# pixelAdapter_f103c8.net
KiCad netlist of a schematic drawn in EAGLE
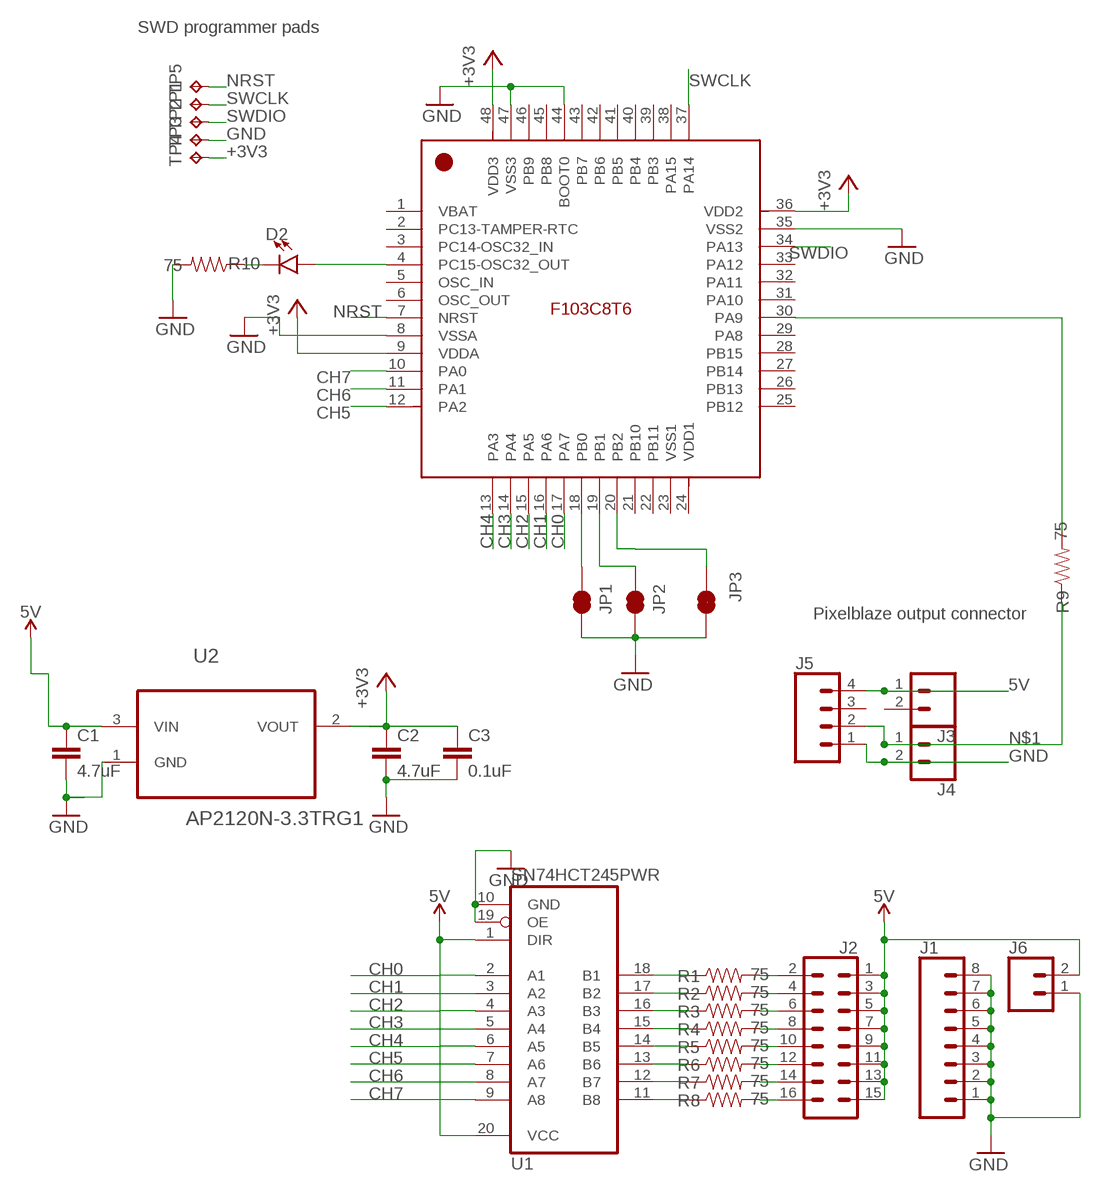
[diagram p0: schematic, sheet 1]

(export (version "E")
  (design (tool "Eeschema 10.0.6"))
  (components
    (comp (ref "C1")
      (value "4.7uF")
      (footprint "eagle-import:0603")
      (libsource (lib "eagle-import") (part "4.7UF0603"))
    )
    (comp (ref "C2")
      (value "4.7uF")
      (footprint "eagle-import:0603")
      (libsource (lib "eagle-import") (part "4.7UF0603"))
    )
    (comp (ref "C3")
      (value "0.1uF")
      (footprint "eagle-import:0603")
      (libsource (lib "eagle-import") (part "0.1UF-0603-25V-(+80/-20%)"))
    )
    (comp (ref "D2")
      (value "LED0603")
      (footprint "eagle-import:LED-0603")
      (libsource (lib "eagle-import") (part "LED0603"))
    )
    (comp (ref "J1")
      (value "CONN_08\"")
      (footprint "eagle-import:1X08")
      (libsource (lib "eagle-import") (part "CONN_08{dblquote}"))
    )
    (comp (ref "J2")
      (value "CONN_08X2")
      (footprint "eagle-import:2X8")
      (libsource (lib "eagle-import") (part "CONN_08X2"))
    )
    (comp (ref "J3")
      (value "CONN_025MM")
      (footprint "eagle-import:SCREWTERMINAL-5MM-2")
      (libsource (lib "eagle-import") (part "bens_CONN_025MM"))
    )
    (comp (ref "J4")
      (value "CONN_025MM")
      (footprint "eagle-import:SCREWTERMINAL-5MM-2")
      (libsource (lib "eagle-import") (part "bens_CONN_025MM"))
    )
    (comp (ref "J5")
      (value "CONN_04LOCK")
      (footprint "eagle-import:1X04_LOCK")
      (libsource (lib "eagle-import") (part "CONN_04LOCK"))
    )
    (comp (ref "J6")
      (value "CONN_02")
      (footprint "eagle-import:1X02")
      (libsource (lib "eagle-import") (part "CONN_02"))
    )
    (comp (ref "JP1")
      (value "JUMPER-SMT_2_NC_TRACE_SILK")
      (footprint "eagle-import:SMT-JUMPER_2_NC_TRACE_SILK")
      (libsource (lib "eagle-import") (part "JUMPER-SMT_2_NC_TRACE_SILK"))
    )
    (comp (ref "JP2")
      (value "JUMPER-SMT_2_NC_TRACE_SILK")
      (footprint "eagle-import:SMT-JUMPER_2_NC_TRACE_SILK")
      (libsource (lib "eagle-import") (part "JUMPER-SMT_2_NC_TRACE_SILK"))
    )
    (comp (ref "JP3")
      (value "JUMPER-SMT_2_NC_TRACE_SILK")
      (footprint "eagle-import:SMT-JUMPER_2_NC_TRACE_SILK")
      (libsource (lib "eagle-import") (part "JUMPER-SMT_2_NC_TRACE_SILK"))
    )
    (comp (ref "R1")
      (value "75")
      (footprint "eagle-import:0603")
      (libsource (lib "eagle-import") (part "100OHM-0603-1/4W-5%"))
    )
    (comp (ref "R2")
      (value "75")
      (footprint "eagle-import:0603")
      (libsource (lib "eagle-import") (part "100OHM-0603-1/4W-5%"))
    )
    (comp (ref "R3")
      (value "75")
      (footprint "eagle-import:0603")
      (libsource (lib "eagle-import") (part "100OHM-0603-1/4W-5%"))
    )
    (comp (ref "R4")
      (value "75")
      (footprint "eagle-import:0603")
      (libsource (lib "eagle-import") (part "100OHM-0603-1/4W-5%"))
    )
    (comp (ref "R5")
      (value "75")
      (footprint "eagle-import:0603")
      (libsource (lib "eagle-import") (part "100OHM-0603-1/4W-5%"))
    )
    (comp (ref "R6")
      (value "75")
      (footprint "eagle-import:0603")
      (libsource (lib "eagle-import") (part "100OHM-0603-1/4W-5%"))
    )
    (comp (ref "R7")
      (value "75")
      (footprint "eagle-import:0603")
      (libsource (lib "eagle-import") (part "100OHM-0603-1/4W-5%"))
    )
    (comp (ref "R8")
      (value "75")
      (footprint "eagle-import:0603")
      (libsource (lib "eagle-import") (part "100OHM-0603-1/4W-5%"))
    )
    (comp (ref "R9")
      (value "75")
      (footprint "eagle-import:0603")
      (libsource (lib "eagle-import") (part "100OHM-0603-1/4W-5%"))
    )
    (comp (ref "R10")
      (value "75")
      (footprint "eagle-import:0603")
      (libsource (lib "eagle-import") (part "100OHM-0603-1/4W-5%"))
    )
    (comp (ref "TP1")
      (value "TPTP20SQ")
      (footprint "eagle-import:TP20SQ")
      (libsource (lib "eagle-import") (part "TPTP20SQ"))
    )
    (comp (ref "TP2")
      (value "TPTP20SQ")
      (footprint "eagle-import:TP20SQ")
      (libsource (lib "eagle-import") (part "TPTP20SQ"))
    )
    (comp (ref "TP3")
      (value "TPTP20SQ")
      (footprint "eagle-import:TP20SQ")
      (libsource (lib "eagle-import") (part "TPTP20SQ"))
    )
    (comp (ref "TP4")
      (value "TPTP20SQ")
      (footprint "eagle-import:TP20SQ")
      (libsource (lib "eagle-import") (part "TPTP20SQ"))
    )
    (comp (ref "TP5")
      (value "TPTP20SQ")
      (footprint "eagle-import:TP20SQ")
      (libsource (lib "eagle-import") (part "TPTP20SQ"))
    )
    (comp (ref "U$1")
      (value "STM32F103C8T6")
      (footprint "eagle-import:LQFP48_7X7MM_0.5MMPP")
      (fields (field (name "MF") "STMicroelectronics"))
      (libsource (lib "eagle-import") (part "STM32F103C8T6"))
    )
    (comp (ref "U1")
      (value "SN74HCT245PWR")
      (footprint "eagle-import:TSSOP20")
      (libsource (lib "eagle-import") (part "74245PW"))
    )
    (comp (ref "U2")
      (value "AP2120N-3.3TRG1")
      (footprint "eagle-import:SOT95P237X112-3N")
      (fields (field (name "MPN") "MCP1700T-3302E/TT"))
      (libsource (lib "eagle-import") (part "MCP1700T-3302E/TT"))
    )
  )
  (nets
    (net (code "1") (name "+3V3") (class "Default")
      (node (ref "C2") (pin "1") (pinfunction "1_1") (pintype "passive"))
      (node (ref "C3") (pin "1") (pinfunction "1_1") (pintype "passive"))
      (node (ref "TP4") (pin "TP") (pinfunction "TP_TP") (pintype "input"))
      (node (ref "U$1") (pin "36") (pinfunction "VDD2_36") (pintype "bidirectional"))
      (node (ref "U$1") (pin "48") (pinfunction "VDD3_48") (pintype "bidirectional"))
      (node (ref "U$1") (pin "9") (pinfunction "VDDA_9") (pintype "bidirectional"))
      (node (ref "U2") (pin "2") (pinfunction "VOUT_2") (pintype "output"))
    )
    (net (code "2") (name "/CH0") (class "Default")
      (node (ref "U$1") (pin "17") (pinfunction "PA7_17") (pintype "bidirectional"))
      (node (ref "U1") (pin "2") (pinfunction "A1_2") (pintype "bidirectional"))
    )
    (net (code "3") (name "/CH1") (class "Default")
      (node (ref "U$1") (pin "16") (pinfunction "PA6_16") (pintype "bidirectional"))
      (node (ref "U1") (pin "3") (pinfunction "A2_3") (pintype "bidirectional"))
    )
    (net (code "4") (name "/CH2") (class "Default")
      (node (ref "U$1") (pin "15") (pinfunction "PA5_15") (pintype "bidirectional"))
      (node (ref "U1") (pin "4") (pinfunction "A3_4") (pintype "bidirectional"))
    )
    (net (code "5") (name "/CH3") (class "Default")
      (node (ref "U$1") (pin "14") (pinfunction "PA4_14") (pintype "bidirectional"))
      (node (ref "U1") (pin "5") (pinfunction "A4_5") (pintype "bidirectional"))
    )
    (net (code "6") (name "/CH4") (class "Default")
      (node (ref "U$1") (pin "13") (pinfunction "PA3_13") (pintype "bidirectional"))
      (node (ref "U1") (pin "6") (pinfunction "A5_6") (pintype "bidirectional"))
    )
    (net (code "7") (name "/CH5") (class "Default")
      (node (ref "U$1") (pin "12") (pinfunction "PA2_12") (pintype "bidirectional"))
      (node (ref "U1") (pin "7") (pinfunction "A6_7") (pintype "bidirectional"))
    )
    (net (code "8") (name "/CH6") (class "Default")
      (node (ref "U$1") (pin "11") (pinfunction "PA1_11") (pintype "bidirectional"))
      (node (ref "U1") (pin "8") (pinfunction "A7_8") (pintype "bidirectional"))
    )
    (net (code "9") (name "/CH7") (class "Default")
      (node (ref "U$1") (pin "10") (pinfunction "PA0_10") (pintype "bidirectional"))
      (node (ref "U1") (pin "9") (pinfunction "A8_9") (pintype "bidirectional"))
    )
    (net (code "10") (name "/N$1") (class "Default")
      (node (ref "J4") (pin "1") (pinfunction "1_1") (pintype "passive"))
      (node (ref "J5") (pin "2") (pinfunction "2_2") (pintype "passive"))
      (node (ref "R9") (pin "1") (pinfunction "1_1") (pintype "passive"))
    )
    (net (code "11") (name "/NRST") (class "Default")
      (node (ref "TP5") (pin "TP") (pinfunction "TP_TP") (pintype "input"))
      (node (ref "U$1") (pin "7") (pinfunction "NRST_7") (pintype "bidirectional"))
    )
    (net (code "12") (name "/SWCLK") (class "Default")
      (node (ref "TP1") (pin "TP") (pinfunction "TP_TP") (pintype "input"))
      (node (ref "U$1") (pin "37") (pinfunction "PA14_37") (pintype "bidirectional"))
    )
    (net (code "13") (name "/SWDIO") (class "Default")
      (node (ref "TP2") (pin "TP") (pinfunction "TP_TP") (pintype "input"))
      (node (ref "U$1") (pin "34") (pinfunction "PA13_34") (pintype "bidirectional"))
    )
    (net (code "14") (name "5V") (class "Default")
      (node (ref "C1") (pin "1") (pinfunction "1_1") (pintype "passive"))
      (node (ref "J2") (pin "1") (pinfunction "1_1") (pintype "passive"))
      (node (ref "J2") (pin "11") (pinfunction "11_11") (pintype "passive"))
      (node (ref "J2") (pin "13") (pinfunction "13_13") (pintype "passive"))
      (node (ref "J2") (pin "15") (pinfunction "15_15") (pintype "passive"))
      (node (ref "J2") (pin "3") (pinfunction "3_3") (pintype "passive"))
      (node (ref "J2") (pin "5") (pinfunction "5_5") (pintype "passive"))
      (node (ref "J2") (pin "7") (pinfunction "7_7") (pintype "passive"))
      (node (ref "J2") (pin "9") (pinfunction "9_9") (pintype "passive"))
      (node (ref "J3") (pin "1") (pinfunction "1_1") (pintype "passive"))
      (node (ref "J5") (pin "4") (pinfunction "4_4") (pintype "passive"))
      (node (ref "J6") (pin "2") (pinfunction "2_2") (pintype "passive"))
      (node (ref "U1") (pin "1") (pinfunction "DIR_1") (pintype "input"))
      (node (ref "U1") (pin "20") (pinfunction "VCC_20") (pintype "bidirectional"))
      (node (ref "U2") (pin "3") (pinfunction "VIN_3") (pintype "input"))
    )
    (net (code "15") (name "GND") (class "Default")
      (node (ref "C1") (pin "2") (pinfunction "2_2") (pintype "passive"))
      (node (ref "C2") (pin "2") (pinfunction "2_2") (pintype "passive"))
      (node (ref "C3") (pin "2") (pinfunction "2_2") (pintype "passive"))
      (node (ref "J1") (pin "1") (pinfunction "1_1") (pintype "passive"))
      (node (ref "J1") (pin "2") (pinfunction "2_2") (pintype "passive"))
      (node (ref "J1") (pin "3") (pinfunction "3_3") (pintype "passive"))
      (node (ref "J1") (pin "4") (pinfunction "4_4") (pintype "passive"))
      (node (ref "J1") (pin "5") (pinfunction "5_5") (pintype "passive"))
      (node (ref "J1") (pin "6") (pinfunction "6_6") (pintype "passive"))
      (node (ref "J1") (pin "7") (pinfunction "7_7") (pintype "passive"))
      (node (ref "J1") (pin "8") (pinfunction "8_8") (pintype "passive"))
      (node (ref "J4") (pin "2") (pinfunction "2_2") (pintype "passive"))
      (node (ref "J5") (pin "1") (pinfunction "1_1") (pintype "passive"))
      (node (ref "J6") (pin "1") (pinfunction "1_1") (pintype "passive"))
      (node (ref "JP1") (pin "2") (pinfunction "2_2") (pintype "passive"))
      (node (ref "JP2") (pin "2") (pinfunction "2_2") (pintype "passive"))
      (node (ref "JP3") (pin "1") (pinfunction "1_1") (pintype "passive"))
      (node (ref "R10") (pin "2") (pinfunction "2_2") (pintype "passive"))
      (node (ref "TP3") (pin "TP") (pinfunction "TP_TP") (pintype "input"))
      (node (ref "U$1") (pin "35") (pinfunction "VSS2_35") (pintype "bidirectional"))
      (node (ref "U$1") (pin "44") (pinfunction "BOOT0_44") (pintype "bidirectional"))
      (node (ref "U$1") (pin "47") (pinfunction "VSS3_47") (pintype "bidirectional"))
      (node (ref "U$1") (pin "8") (pinfunction "VSSA_8") (pintype "bidirectional"))
      (node (ref "U1") (pin "10") (pinfunction "GND_10") (pintype "bidirectional"))
      (node (ref "U1") (pin "19") (pinfunction "OE_19") (pintype "input"))
      (node (ref "U2") (pin "1") (pinfunction "GND_1") (pintype "passive"))
    )
    (net (code "16") (name "Net-(D2-PadC)") (class "Default")
      (node (ref "D2") (pin "C") (pinfunction "C_C") (pintype "passive"))
      (node (ref "R10") (pin "1") (pinfunction "1_1") (pintype "passive"))
    )
    (net (code "17") (name "Net-(J2-Pad2)") (class "Default")
      (node (ref "J2") (pin "2") (pinfunction "2_2") (pintype "passive"))
      (node (ref "R1") (pin "2") (pinfunction "2_2") (pintype "passive"))
    )
    (net (code "18") (name "Net-(J2-Pad4)") (class "Default")
      (node (ref "J2") (pin "4") (pinfunction "4_4") (pintype "passive"))
      (node (ref "R2") (pin "2") (pinfunction "2_2") (pintype "passive"))
    )
    (net (code "19") (name "Net-(J2-Pad6)") (class "Default")
      (node (ref "J2") (pin "6") (pinfunction "6_6") (pintype "passive"))
      (node (ref "R3") (pin "2") (pinfunction "2_2") (pintype "passive"))
    )
    (net (code "20") (name "Net-(J2-Pad8)") (class "Default")
      (node (ref "J2") (pin "8") (pinfunction "8_8") (pintype "passive"))
      (node (ref "R4") (pin "2") (pinfunction "2_2") (pintype "passive"))
    )
    (net (code "21") (name "Net-(J2-Pad10)") (class "Default")
      (node (ref "J2") (pin "10") (pinfunction "10_10") (pintype "passive"))
      (node (ref "R5") (pin "2") (pinfunction "2_2") (pintype "passive"))
    )
    (net (code "22") (name "Net-(J2-Pad12)") (class "Default")
      (node (ref "J2") (pin "12") (pinfunction "12_12") (pintype "passive"))
      (node (ref "R6") (pin "2") (pinfunction "2_2") (pintype "passive"))
    )
    (net (code "23") (name "Net-(J2-Pad14)") (class "Default")
      (node (ref "J2") (pin "14") (pinfunction "14_14") (pintype "passive"))
      (node (ref "R7") (pin "2") (pinfunction "2_2") (pintype "passive"))
    )
    (net (code "24") (name "Net-(J2-Pad16)") (class "Default")
      (node (ref "J2") (pin "16") (pinfunction "16_16") (pintype "passive"))
      (node (ref "R8") (pin "2") (pinfunction "2_2") (pintype "passive"))
    )
    (net (code "25") (name "Net-(U$1-PA9)") (class "Default")
      (node (ref "R9") (pin "2") (pinfunction "2_2") (pintype "passive"))
      (node (ref "U$1") (pin "30") (pinfunction "PA9_30") (pintype "bidirectional"))
    )
    (net (code "26") (name "Net-(U$1-PB0)") (class "Default")
      (node (ref "JP1") (pin "1") (pinfunction "1_1") (pintype "passive"))
      (node (ref "U$1") (pin "18") (pinfunction "PB0_18") (pintype "bidirectional"))
    )
    (net (code "27") (name "Net-(U$1-PB1)") (class "Default")
      (node (ref "JP2") (pin "1") (pinfunction "1_1") (pintype "passive"))
      (node (ref "U$1") (pin "19") (pinfunction "PB1_19") (pintype "bidirectional"))
    )
    (net (code "28") (name "Net-(U$1-PB2)") (class "Default")
      (node (ref "JP3") (pin "2") (pinfunction "2_2") (pintype "passive"))
      (node (ref "U$1") (pin "20") (pinfunction "PB2_20") (pintype "bidirectional"))
    )
    (net (code "29") (name "Net-(U$1-PC15-OSC32_OUT)") (class "Default")
      (node (ref "D2") (pin "A") (pinfunction "A_A") (pintype "passive"))
      (node (ref "U$1") (pin "4") (pinfunction "PC15-OSC32_OUT_4") (pintype "bidirectional"))
    )
    (net (code "30") (name "Net-(U1-B1)") (class "Default")
      (node (ref "R1") (pin "1") (pinfunction "1_1") (pintype "passive"))
      (node (ref "U1") (pin "18") (pinfunction "B1_18") (pintype "bidirectional"))
    )
    (net (code "31") (name "Net-(U1-B2)") (class "Default")
      (node (ref "R2") (pin "1") (pinfunction "1_1") (pintype "passive"))
      (node (ref "U1") (pin "17") (pinfunction "B2_17") (pintype "bidirectional"))
    )
    (net (code "32") (name "Net-(U1-B3)") (class "Default")
      (node (ref "R3") (pin "1") (pinfunction "1_1") (pintype "passive"))
      (node (ref "U1") (pin "16") (pinfunction "B3_16") (pintype "bidirectional"))
    )
    (net (code "33") (name "Net-(U1-B4)") (class "Default")
      (node (ref "R4") (pin "1") (pinfunction "1_1") (pintype "passive"))
      (node (ref "U1") (pin "15") (pinfunction "B4_15") (pintype "bidirectional"))
    )
    (net (code "34") (name "Net-(U1-B5)") (class "Default")
      (node (ref "R5") (pin "1") (pinfunction "1_1") (pintype "passive"))
      (node (ref "U1") (pin "14") (pinfunction "B5_14") (pintype "bidirectional"))
    )
    (net (code "35") (name "Net-(U1-B6)") (class "Default")
      (node (ref "R6") (pin "1") (pinfunction "1_1") (pintype "passive"))
      (node (ref "U1") (pin "13") (pinfunction "B6_13") (pintype "bidirectional"))
    )
    (net (code "36") (name "Net-(U1-B7)") (class "Default")
      (node (ref "R7") (pin "1") (pinfunction "1_1") (pintype "passive"))
      (node (ref "U1") (pin "12") (pinfunction "B7_12") (pintype "bidirectional"))
    )
    (net (code "37") (name "Net-(U1-B8)") (class "Default")
      (node (ref "R8") (pin "1") (pinfunction "1_1") (pintype "passive"))
      (node (ref "U1") (pin "11") (pinfunction "B8_11") (pintype "bidirectional"))
    )
    (net (code "38") (name "unconnected-(J3-Pad2)") (class "Default")
      (node (ref "J3") (pin "2") (pinfunction "2_2") (pintype "passive"))
    )
    (net (code "39") (name "unconnected-(J5-Pad3)") (class "Default")
      (node (ref "J5") (pin "3") (pinfunction "3_3") (pintype "passive"))
    )
    (net (code "40") (name "unconnected-(U$1-OSC_IN-Pad5)") (class "Default")
      (node (ref "U$1") (pin "5") (pinfunction "OSC_IN_5") (pintype "bidirectional"))
    )
    (net (code "41") (name "unconnected-(U$1-OSC_OUT-Pad6)") (class "Default")
      (node (ref "U$1") (pin "6") (pinfunction "OSC_OUT_6") (pintype "bidirectional"))
    )
    (net (code "42") (name "unconnected-(U$1-PA8-Pad29)") (class "Default")
      (node (ref "U$1") (pin "29") (pinfunction "PA8_29") (pintype "bidirectional"))
    )
    (net (code "43") (name "unconnected-(U$1-PA10-Pad31)") (class "Default")
      (node (ref "U$1") (pin "31") (pinfunction "PA10_31") (pintype "bidirectional"))
    )
    (net (code "44") (name "unconnected-(U$1-PA11-Pad32)") (class "Default")
      (node (ref "U$1") (pin "32") (pinfunction "PA11_32") (pintype "bidirectional"))
    )
    (net (code "45") (name "unconnected-(U$1-PA12-Pad33)") (class "Default")
      (node (ref "U$1") (pin "33") (pinfunction "PA12_33") (pintype "bidirectional"))
    )
    (net (code "46") (name "unconnected-(U$1-PA15-Pad38)") (class "Default")
      (node (ref "U$1") (pin "38") (pinfunction "PA15_38") (pintype "bidirectional"))
    )
    (net (code "47") (name "unconnected-(U$1-PB3-Pad39)") (class "Default")
      (node (ref "U$1") (pin "39") (pinfunction "PB3_39") (pintype "bidirectional"))
    )
    (net (code "48") (name "unconnected-(U$1-PB4-Pad40)") (class "Default")
      (node (ref "U$1") (pin "40") (pinfunction "PB4_40") (pintype "bidirectional"))
    )
    (net (code "49") (name "unconnected-(U$1-PB5-Pad41)") (class "Default")
      (node (ref "U$1") (pin "41") (pinfunction "PB5_41") (pintype "bidirectional"))
    )
    (net (code "50") (name "unconnected-(U$1-PB6-Pad42)") (class "Default")
      (node (ref "U$1") (pin "42") (pinfunction "PB6_42") (pintype "bidirectional"))
    )
    (net (code "51") (name "unconnected-(U$1-PB7-Pad43)") (class "Default")
      (node (ref "U$1") (pin "43") (pinfunction "PB7_43") (pintype "bidirectional"))
    )
    (net (code "52") (name "unconnected-(U$1-PB8-Pad45)") (class "Default")
      (node (ref "U$1") (pin "45") (pinfunction "PB8_45") (pintype "bidirectional"))
    )
    (net (code "53") (name "unconnected-(U$1-PB9-Pad46)") (class "Default")
      (node (ref "U$1") (pin "46") (pinfunction "PB9_46") (pintype "bidirectional"))
    )
    (net (code "54") (name "unconnected-(U$1-PB10-Pad21)") (class "Default")
      (node (ref "U$1") (pin "21") (pinfunction "PB10_21") (pintype "bidirectional"))
    )
    (net (code "55") (name "unconnected-(U$1-PB11-Pad22)") (class "Default")
      (node (ref "U$1") (pin "22") (pinfunction "PB11_22") (pintype "bidirectional"))
    )
    (net (code "56") (name "unconnected-(U$1-PB12-Pad25)") (class "Default")
      (node (ref "U$1") (pin "25") (pinfunction "PB12_25") (pintype "bidirectional"))
    )
    (net (code "57") (name "unconnected-(U$1-PB13-Pad26)") (class "Default")
      (node (ref "U$1") (pin "26") (pinfunction "PB13_26") (pintype "bidirectional"))
    )
    (net (code "58") (name "unconnected-(U$1-PB14-Pad27)") (class "Default")
      (node (ref "U$1") (pin "27") (pinfunction "PB14_27") (pintype "bidirectional"))
    )
    (net (code "59") (name "unconnected-(U$1-PB15-Pad28)") (class "Default")
      (node (ref "U$1") (pin "28") (pinfunction "PB15_28") (pintype "bidirectional"))
    )
    (net (code "60") (name "unconnected-(U$1-PC13-TAMPER-RTC-Pad2)") (class "Default")
      (node (ref "U$1") (pin "2") (pinfunction "PC13-TAMPER-RTC_2") (pintype "bidirectional"))
    )
    (net (code "61") (name "unconnected-(U$1-PC14-OSC32_IN-Pad3)") (class "Default")
      (node (ref "U$1") (pin "3") (pinfunction "PC14-OSC32_IN_3") (pintype "bidirectional"))
    )
    (net (code "62") (name "unconnected-(U$1-VBAT-Pad1)") (class "Default")
      (node (ref "U$1") (pin "1") (pinfunction "VBAT_1") (pintype "bidirectional"))
    )
    (net (code "63") (name "unconnected-(U$1-VDD1-Pad24)") (class "Default")
      (node (ref "U$1") (pin "24") (pinfunction "VDD1_24") (pintype "bidirectional"))
    )
    (net (code "64") (name "unconnected-(U$1-VSS1-Pad23)") (class "Default")
      (node (ref "U$1") (pin "23") (pinfunction "VSS1_23") (pintype "bidirectional"))
    )
  )
)
